# NG2094_EEPROM.net
KiCad netlist of a schematic drawn in Altium Designer
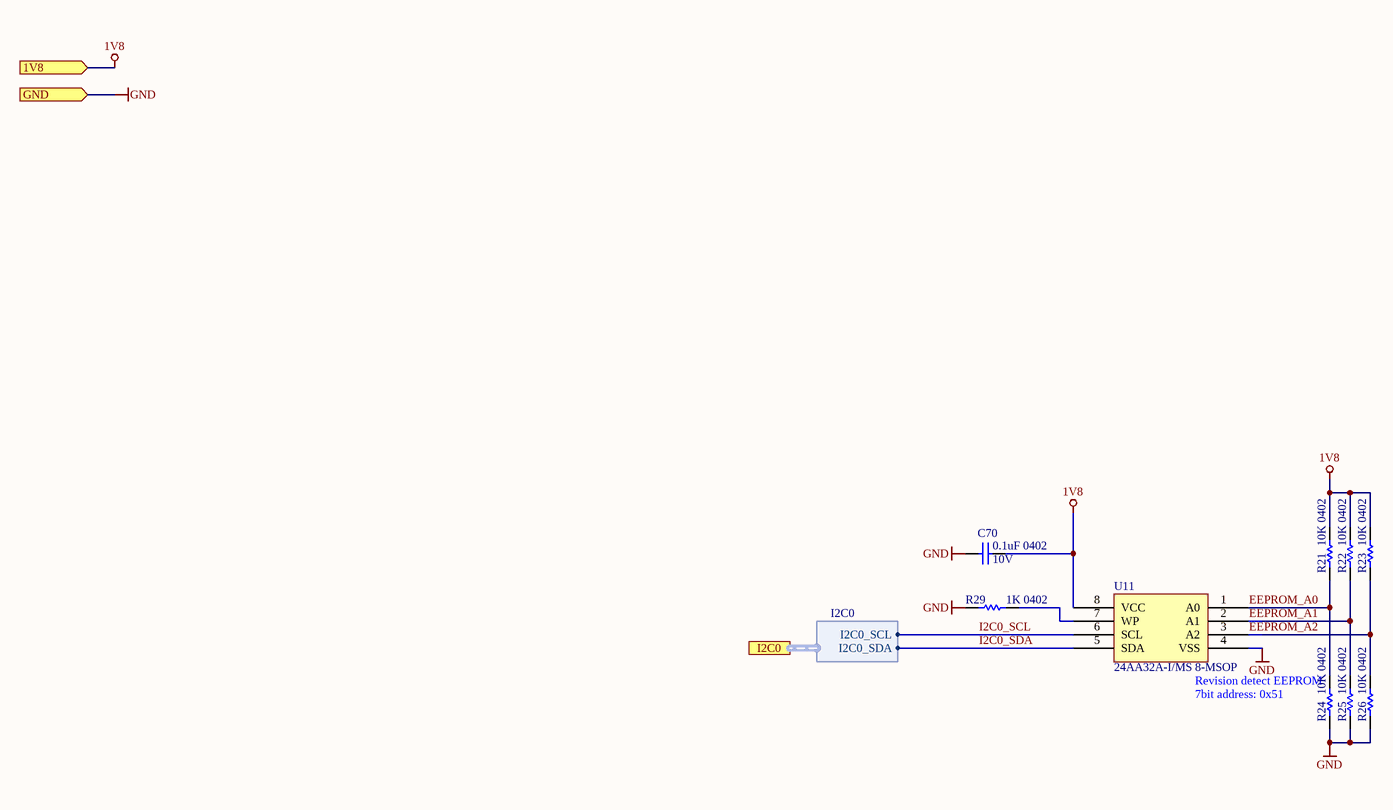
[diagram p0: NG2094_EEPROM.SchDoc]

(export (version "E")
  (design (tool "Eeschema 10.0.6"))
  (components
    (comp (ref "C70")
      (value "0.1uF 0402")
      (footprint "CAP_Altium_Vault_Generic:CAPC0402(1005)70_L")
      (description "CAP CER 0.1UF 10V X7R 0402 5%")
      (fields (field (name "TOLERANCE") "5%") (field (name "VOLTAGE RATING") "10V"))
      (libsource (lib "LuxonisMaster") (part "GRM155R71A104JA01D"))
    )
    (comp (ref "R21")
      (value "10K 0402")
      (footprint "RES_Altium_Vault_Generic:RESC0402(1005)_L")
      (fields (field (name "TOLERANCE") "1%"))
      (libsource (lib "LuxonisMaster") (part "RC0402FR-1310KL"))
    )
    (comp (ref "R22")
      (value "10K 0402")
      (footprint "RES_Altium_Vault_Generic:RESC0402(1005)_L")
      (fields (field (name "TOLERANCE") "1%"))
      (libsource (lib "LuxonisMaster") (part "RC0402FR-1310KL"))
    )
    (comp (ref "R23")
      (value "10K 0402")
      (footprint "RES_Altium_Vault_Generic:RESC0402(1005)_L")
      (fields (field (name "TOLERANCE") "1%"))
      (libsource (lib "LuxonisMaster") (part "RC0402FR-1310KL"))
    )
    (comp (ref "R24")
      (value "10K 0402")
      (footprint "RES_Altium_Vault_Generic:RESC0402(1005)_L")
      (fields (field (name "TOLERANCE") "1%"))
      (libsource (lib "LuxonisMaster") (part "RC0402FR-1310KL"))
    )
    (comp (ref "R25")
      (value "10K 0402")
      (footprint "RES_Altium_Vault_Generic:RESC0402(1005)_L")
      (fields (field (name "TOLERANCE") "1%"))
      (libsource (lib "LuxonisMaster") (part "RC0402FR-1310KL"))
    )
    (comp (ref "R26")
      (value "10K 0402")
      (footprint "RES_Altium_Vault_Generic:RESC0402(1005)_L")
      (fields (field (name "TOLERANCE") "1%"))
      (libsource (lib "LuxonisMaster") (part "RC0402FR-1310KL"))
    )
    (comp (ref "R29")
      (value "1K 0402")
      (footprint "RES_Altium_Vault_Generic:RESC0402(1005)_L")
      (fields (field (name "TOLERANCE") "1%"))
      (libsource (lib "LuxonisMaster") (part "RC0402FR-071KL"))
    )
    (comp (ref "U11")
      (value "24AA32A-I/MS 8-MSOP")
      (footprint "LuxonisMaster:24AA32A-I/MS")
      (description "IC EEPROM 32K I2C 400KHZ 8MSOP Memory IC 32Kb (4K x 8) I²C 400kHz 900ns 8-MSOP")
      (libsource (lib "LuxonisMaster") (part "24AA32A-I/MS"))
    )
  )
  (nets
    (net (code "2") (name "/EEPROM_A0") (class "Default")
      (node (ref "R21") (pin "1") (pinfunction "1_1") (pintype "passive"))
      (node (ref "R24") (pin "2") (pinfunction "2_2") (pintype "passive"))
      (node (ref "U11") (pin "1") (pinfunction "A0_1") (pintype "passive"))
    )
    (net (code "3") (name "/EEPROM_A1") (class "Default")
      (node (ref "R22") (pin "1") (pinfunction "1_1") (pintype "passive"))
      (node (ref "R25") (pin "2") (pinfunction "2_2") (pintype "passive"))
      (node (ref "U11") (pin "2") (pinfunction "A1_2") (pintype "passive"))
    )
    (net (code "4") (name "/EEPROM_A2") (class "Default")
      (node (ref "R23") (pin "1") (pinfunction "1_1") (pintype "passive"))
      (node (ref "R26") (pin "2") (pinfunction "2_2") (pintype "passive"))
      (node (ref "U11") (pin "3") (pinfunction "A2_3") (pintype "passive"))
    )
    (net (code "5") (name "/I2C0_SCL") (class "Default")
      (node (ref "U11") (pin "6") (pinfunction "SCL_6") (pintype "passive"))
    )
    (net (code "6") (name "/I2C0_SDA") (class "Default")
      (node (ref "U11") (pin "5") (pinfunction "SDA_5") (pintype "passive"))
    )
    (net (code "8") (name "1V8") (class "Default")
      (node (ref "C70") (pin "2") (pinfunction "2_2") (pintype "passive"))
      (node (ref "R21") (pin "2") (pinfunction "2_2") (pintype "passive"))
      (node (ref "R22") (pin "2") (pinfunction "2_2") (pintype "passive"))
      (node (ref "R23") (pin "2") (pinfunction "2_2") (pintype "passive"))
      (node (ref "U11") (pin "8") (pinfunction "VCC_8") (pintype "passive"))
    )
    (net (code "9") (name "GND") (class "Default")
      (node (ref "C70") (pin "1") (pinfunction "1_1") (pintype "passive"))
      (node (ref "R24") (pin "1") (pinfunction "1_1") (pintype "passive"))
      (node (ref "R25") (pin "1") (pinfunction "1_1") (pintype "passive"))
      (node (ref "R26") (pin "1") (pinfunction "1_1") (pintype "passive"))
      (node (ref "R29") (pin "1") (pinfunction "1_1") (pintype "passive"))
      (node (ref "U11") (pin "4") (pinfunction "VSS_4") (pintype "passive"))
    )
    (net (code "10") (name "Net-(U11-WP)") (class "Default")
      (node (ref "R29") (pin "2") (pinfunction "2_2") (pintype "passive"))
      (node (ref "U11") (pin "7") (pinfunction "WP_7") (pintype "passive"))
    )
  )
)
